# spin.net
KiCad netlist of a schematic drawn in EAGLE
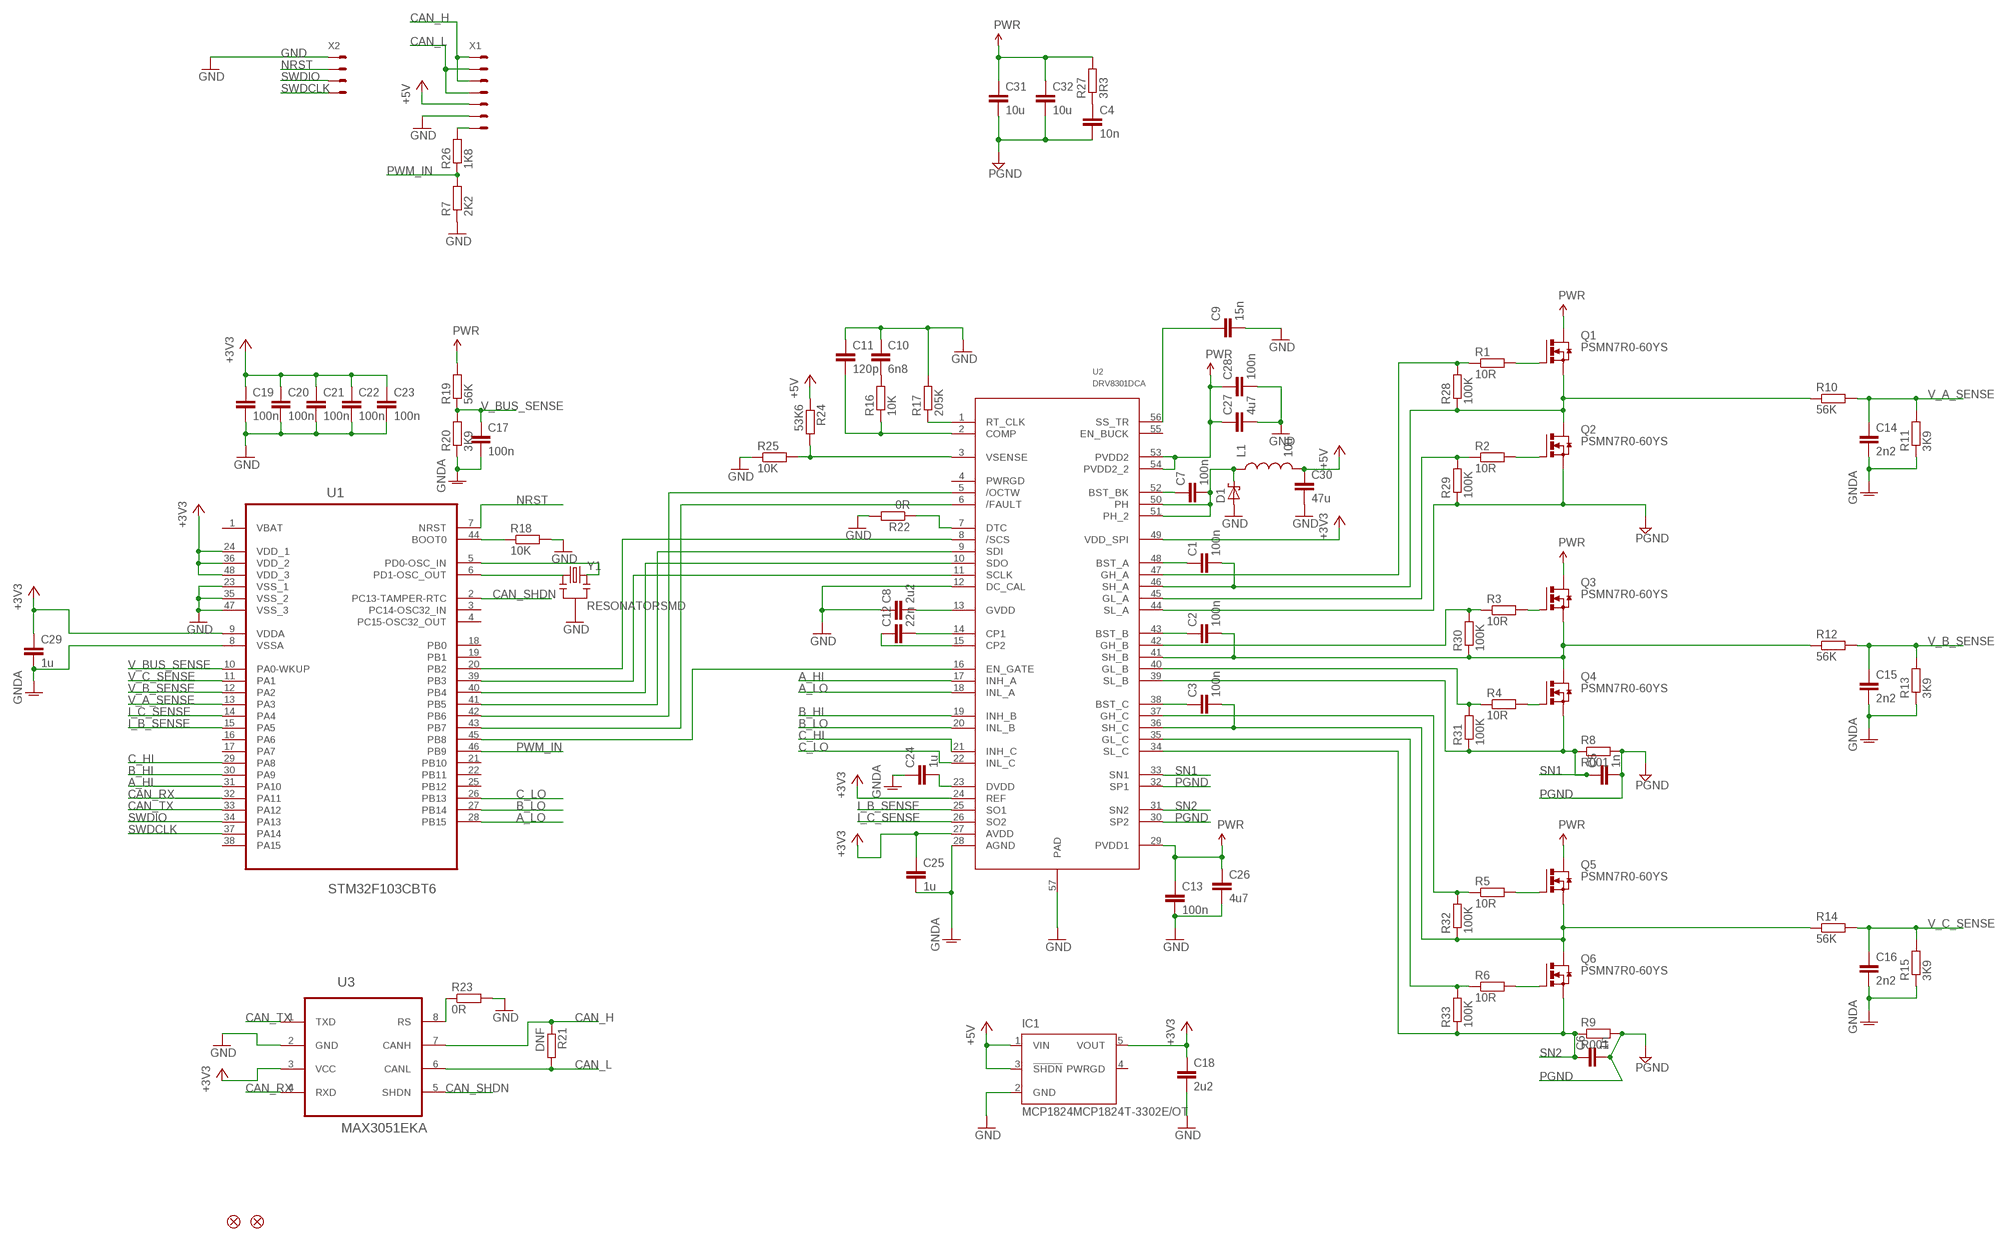
[diagram p0: schematic, sheet 1]

(export (version "E")
  (design (tool "Eeschema 10.0.6"))
  (components
    (comp (ref "C1")
      (value "100n")
      (footprint "eagle-import:C0603")
      (libsource (lib "eagle-import") (part "C-EUC0603"))
    )
    (comp (ref "C2")
      (value "100n")
      (footprint "eagle-import:C0603")
      (libsource (lib "eagle-import") (part "C-EUC0603"))
    )
    (comp (ref "C3")
      (value "100n")
      (footprint "eagle-import:C0603")
      (libsource (lib "eagle-import") (part "C-EUC0603"))
    )
    (comp (ref "C4")
      (value "10n")
      (footprint "eagle-import:C0603")
      (libsource (lib "eagle-import") (part "C-EUC0603"))
    )
    (comp (ref "C5")
      (value "1n")
      (footprint "eagle-import:C0603")
      (libsource (lib "eagle-import") (part "C-EUC0603"))
    )
    (comp (ref "C6")
      (value "1n")
      (footprint "eagle-import:C0603")
      (libsource (lib "eagle-import") (part "C-EUC0603"))
    )
    (comp (ref "C7")
      (value "100n")
      (footprint "eagle-import:C0603")
      (libsource (lib "eagle-import") (part "C-EUC0603"))
    )
    (comp (ref "C8")
      (value "2u2")
      (footprint "eagle-import:C0603")
      (libsource (lib "eagle-import") (part "C-EUC0603"))
    )
    (comp (ref "C9")
      (value "15n")
      (footprint "eagle-import:C0603")
      (libsource (lib "eagle-import") (part "C-EUC0603"))
    )
    (comp (ref "C10")
      (value "6n8")
      (footprint "eagle-import:C0603")
      (libsource (lib "eagle-import") (part "C-EUC0603"))
    )
    (comp (ref "C11")
      (value "120p")
      (footprint "eagle-import:C0603")
      (libsource (lib "eagle-import") (part "C-EUC0603"))
    )
    (comp (ref "C12")
      (value "22n")
      (footprint "eagle-import:C0603")
      (libsource (lib "eagle-import") (part "C-EUC0603"))
    )
    (comp (ref "C13")
      (value "100n")
      (footprint "eagle-import:C0603")
      (libsource (lib "eagle-import") (part "C-EUC0603"))
    )
    (comp (ref "C14")
      (value "2n2")
      (footprint "eagle-import:C0603")
      (libsource (lib "eagle-import") (part "C-EUC0603"))
    )
    (comp (ref "C15")
      (value "2n2")
      (footprint "eagle-import:C0603")
      (libsource (lib "eagle-import") (part "C-EUC0603"))
    )
    (comp (ref "C16")
      (value "2n2")
      (footprint "eagle-import:C0603")
      (libsource (lib "eagle-import") (part "C-EUC0603"))
    )
    (comp (ref "C17")
      (value "100n")
      (footprint "eagle-import:C0603")
      (libsource (lib "eagle-import") (part "C-EUC0603"))
    )
    (comp (ref "C18")
      (value "2u2")
      (footprint "eagle-import:C0603")
      (libsource (lib "eagle-import") (part "C-EUC0603"))
    )
    (comp (ref "C19")
      (value "100n")
      (footprint "eagle-import:C0603")
      (libsource (lib "eagle-import") (part "C-EUC0603"))
    )
    (comp (ref "C20")
      (value "100n")
      (footprint "eagle-import:C0603")
      (libsource (lib "eagle-import") (part "C-EUC0603"))
    )
    (comp (ref "C21")
      (value "100n")
      (footprint "eagle-import:C0603")
      (libsource (lib "eagle-import") (part "C-EUC0603"))
    )
    (comp (ref "C22")
      (value "100n")
      (footprint "eagle-import:C0603")
      (libsource (lib "eagle-import") (part "C-EUC0603"))
    )
    (comp (ref "C23")
      (value "100n")
      (footprint "eagle-import:C0603")
      (libsource (lib "eagle-import") (part "C-EUC0603"))
    )
    (comp (ref "C24")
      (value "1u")
      (footprint "eagle-import:C0603")
      (libsource (lib "eagle-import") (part "C-EUC0603"))
    )
    (comp (ref "C25")
      (value "1u")
      (footprint "eagle-import:C0603")
      (libsource (lib "eagle-import") (part "C-EUC0603"))
    )
    (comp (ref "C26")
      (value "4u7")
      (footprint "eagle-import:C0805")
      (libsource (lib "eagle-import") (part "C-EUC0805"))
    )
    (comp (ref "C27")
      (value "4u7")
      (footprint "eagle-import:C0805")
      (libsource (lib "eagle-import") (part "C-EUC0805"))
    )
    (comp (ref "C28")
      (value "100n")
      (footprint "eagle-import:C0603")
      (libsource (lib "eagle-import") (part "C-EUC0603"))
    )
    (comp (ref "C29")
      (value "1u")
      (footprint "eagle-import:C0603")
      (libsource (lib "eagle-import") (part "C-EUC0603"))
    )
    (comp (ref "C30")
      (value "47u")
      (footprint "eagle-import:1210")
      (libsource (lib "eagle-import") (part "CAP1210"))
    )
    (comp (ref "C31")
      (value "10u")
      (footprint "eagle-import:1210")
      (libsource (lib "eagle-import") (part "CAP1210"))
    )
    (comp (ref "C32")
      (value "10u")
      (footprint "eagle-import:1210")
      (libsource (lib "eagle-import") (part "CAP1210"))
    )
    (comp (ref "D1")
      (value "STPS1H100AF")
      (footprint "eagle-import:SMA")
      (libsource (lib "eagle-import") (part "STPS1H100AF"))
    )
    (comp (ref "IC1")
      (value "MCP1824MCP1824T-3302E/OT")
      (footprint "eagle-import:SOT23-5L")
      (libsource (lib "eagle-import") (part "MCP1824MCP1824T-3302E/OT"))
    )
    (comp (ref "JP1")
      (value "FIDUCIALUFIDUCIAL")
      (footprint "eagle-import:MICRO-FIDUCIAL")
      (libsource (lib "eagle-import") (part "FIDUCIALUFIDUCIAL"))
    )
    (comp (ref "JP2")
      (value "FIDUCIALUFIDUCIAL")
      (footprint "eagle-import:MICRO-FIDUCIAL")
      (libsource (lib "eagle-import") (part "FIDUCIALUFIDUCIAL"))
    )
    (comp (ref "L1")
      (value "10u")
      (footprint "eagle-import:NR6028")
      (libsource (lib "eagle-import") (part "INDUCTORNR6028"))
    )
    (comp (ref "Q1")
      (value "PSMN7R0-60YS")
      (footprint "eagle-import:POWER-SO8-UNIVERSAL")
      (libsource (lib "eagle-import") (part "PSMN7R0-60YS"))
    )
    (comp (ref "Q2")
      (value "PSMN7R0-60YS")
      (footprint "eagle-import:POWER-SO8-UNIVERSAL")
      (libsource (lib "eagle-import") (part "PSMN7R0-60YS"))
    )
    (comp (ref "Q3")
      (value "PSMN7R0-60YS")
      (footprint "eagle-import:POWER-SO8-UNIVERSAL")
      (libsource (lib "eagle-import") (part "PSMN7R0-60YS"))
    )
    (comp (ref "Q4")
      (value "PSMN7R0-60YS")
      (footprint "eagle-import:POWER-SO8-UNIVERSAL")
      (libsource (lib "eagle-import") (part "PSMN7R0-60YS"))
    )
    (comp (ref "Q5")
      (value "PSMN7R0-60YS")
      (footprint "eagle-import:POWER-SO8-UNIVERSAL")
      (libsource (lib "eagle-import") (part "PSMN7R0-60YS"))
    )
    (comp (ref "Q6")
      (value "PSMN7R0-60YS")
      (footprint "eagle-import:POWER-SO8-UNIVERSAL")
      (libsource (lib "eagle-import") (part "PSMN7R0-60YS"))
    )
    (comp (ref "R1")
      (value "10R")
      (footprint "eagle-import:R0603")
      (libsource (lib "eagle-import") (part "R-EU_R0603"))
    )
    (comp (ref "R2")
      (value "10R")
      (footprint "eagle-import:R0603")
      (libsource (lib "eagle-import") (part "R-EU_R0603"))
    )
    (comp (ref "R3")
      (value "10R")
      (footprint "eagle-import:R0603")
      (libsource (lib "eagle-import") (part "R-EU_R0603"))
    )
    (comp (ref "R4")
      (value "10R")
      (footprint "eagle-import:R0603")
      (libsource (lib "eagle-import") (part "R-EU_R0603"))
    )
    (comp (ref "R5")
      (value "10R")
      (footprint "eagle-import:R0603")
      (libsource (lib "eagle-import") (part "R-EU_R0603"))
    )
    (comp (ref "R6")
      (value "10R")
      (footprint "eagle-import:R0603")
      (libsource (lib "eagle-import") (part "R-EU_R0603"))
    )
    (comp (ref "R7")
      (value "2K2")
      (footprint "eagle-import:R0603")
      (libsource (lib "eagle-import") (part "R-EU_R0603"))
    )
    (comp (ref "R8")
      (value "R001")
      (footprint "eagle-import:R1210")
      (libsource (lib "eagle-import") (part "R-EU_R1210"))
    )
    (comp (ref "R9")
      (value "R001")
      (footprint "eagle-import:R1210")
      (libsource (lib "eagle-import") (part "R-EU_R1210"))
    )
    (comp (ref "R10")
      (value "56K")
      (footprint "eagle-import:R0603")
      (libsource (lib "eagle-import") (part "R-EU_R0603"))
    )
    (comp (ref "R11")
      (value "3K9")
      (footprint "eagle-import:R0603")
      (libsource (lib "eagle-import") (part "R-EU_R0603"))
    )
    (comp (ref "R12")
      (value "56K")
      (footprint "eagle-import:R0603")
      (libsource (lib "eagle-import") (part "R-EU_R0603"))
    )
    (comp (ref "R13")
      (value "3K9")
      (footprint "eagle-import:R0603")
      (libsource (lib "eagle-import") (part "R-EU_R0603"))
    )
    (comp (ref "R14")
      (value "56K")
      (footprint "eagle-import:R0603")
      (libsource (lib "eagle-import") (part "R-EU_R0603"))
    )
    (comp (ref "R15")
      (value "3K9")
      (footprint "eagle-import:R0603")
      (libsource (lib "eagle-import") (part "R-EU_R0603"))
    )
    (comp (ref "R16")
      (value "10K")
      (footprint "eagle-import:R0603")
      (libsource (lib "eagle-import") (part "R-EU_R0603"))
    )
    (comp (ref "R17")
      (value "205K")
      (footprint "eagle-import:R0603")
      (libsource (lib "eagle-import") (part "R-EU_R0603"))
    )
    (comp (ref "R18")
      (value "10K")
      (footprint "eagle-import:R0603")
      (libsource (lib "eagle-import") (part "R-EU_R0603"))
    )
    (comp (ref "R19")
      (value "56K")
      (footprint "eagle-import:R0603")
      (libsource (lib "eagle-import") (part "R-EU_R0603"))
    )
    (comp (ref "R20")
      (value "3K9")
      (footprint "eagle-import:R0603")
      (libsource (lib "eagle-import") (part "R-EU_R0603"))
    )
    (comp (ref "R21")
      (value "DNF")
      (footprint "eagle-import:R0603")
      (libsource (lib "eagle-import") (part "R-EU_R0603"))
    )
    (comp (ref "R22")
      (value "0R")
      (footprint "eagle-import:R0603")
      (libsource (lib "eagle-import") (part "R-EU_R0603"))
    )
    (comp (ref "R23")
      (value "0R")
      (footprint "eagle-import:R0603")
      (libsource (lib "eagle-import") (part "R-EU_R0603"))
    )
    (comp (ref "R24")
      (value "53K6")
      (footprint "eagle-import:R0603")
      (libsource (lib "eagle-import") (part "R-EU_R0603"))
    )
    (comp (ref "R25")
      (value "10K")
      (footprint "eagle-import:R0603")
      (libsource (lib "eagle-import") (part "R-EU_R0603"))
    )
    (comp (ref "R26")
      (value "1K8")
      (footprint "eagle-import:R0603")
      (libsource (lib "eagle-import") (part "R-EU_R0603"))
    )
    (comp (ref "R27")
      (value "3R3")
      (footprint "eagle-import:R0805")
      (libsource (lib "eagle-import") (part "R-EU_R0805"))
    )
    (comp (ref "R28")
      (value "100K")
      (footprint "eagle-import:R0603")
      (libsource (lib "eagle-import") (part "R-EU_R0603"))
    )
    (comp (ref "R29")
      (value "100K")
      (footprint "eagle-import:R0603")
      (libsource (lib "eagle-import") (part "R-EU_R0603"))
    )
    (comp (ref "R30")
      (value "100K")
      (footprint "eagle-import:R0603")
      (libsource (lib "eagle-import") (part "R-EU_R0603"))
    )
    (comp (ref "R31")
      (value "100K")
      (footprint "eagle-import:R0603")
      (libsource (lib "eagle-import") (part "R-EU_R0603"))
    )
    (comp (ref "R32")
      (value "100K")
      (footprint "eagle-import:R0603")
      (libsource (lib "eagle-import") (part "R-EU_R0603"))
    )
    (comp (ref "R33")
      (value "100K")
      (footprint "eagle-import:R0603")
      (libsource (lib "eagle-import") (part "R-EU_R0603"))
    )
    (comp (ref "U1")
      (value "STM32F103CBT6")
      (footprint "eagle-import:QFP50P900X900X160-48N")
      (libsource (lib "eagle-import") (part "STM32F103CBT6"))
    )
    (comp (ref "U2")
      (value "DRV8301DCA")
      (footprint "eagle-import:TSSOP56P")
      (libsource (lib "eagle-import") (part "DRV8301DCA"))
    )
    (comp (ref "U3")
      (value "MAX3051EKA")
      (footprint "eagle-import:SOT65P280X145-8N")
      (libsource (lib "eagle-import") (part "MAX3051EKA"))
    )
    (comp (ref "X1")
      (value "SM07B-SRSS-TB")
      (footprint "eagle-import:SM07B-SRSS-TB")
      (libsource (lib "eagle-import") (part "?M07B-SRSS-TBS"))
    )
    (comp (ref "X2")
      (value "SM04B-SRSS-TB")
      (footprint "eagle-import:SM04B-SRSS-TB")
      (libsource (lib "eagle-import") (part "?M04B-SRSS-TBS"))
    )
    (comp (ref "Y1")
      (value "RESONATORSMD")
      (footprint "eagle-import:RESONATOR-SMD")
      (libsource (lib "eagle-import") (part "RESONATORSMD"))
    )
  )
  (nets
    (net (code "1") (name "+3V3") (class "Default")
      (node (ref "C18") (pin "1") (pinfunction "1_1") (pintype "passive"))
      (node (ref "C19") (pin "1") (pinfunction "1_1") (pintype "passive"))
      (node (ref "C20") (pin "1") (pinfunction "1_1") (pintype "passive"))
      (node (ref "C21") (pin "1") (pinfunction "1_1") (pintype "passive"))
      (node (ref "C22") (pin "1") (pinfunction "1_1") (pintype "passive"))
      (node (ref "C23") (pin "1") (pinfunction "1_1") (pintype "passive"))
      (node (ref "C25") (pin "1") (pinfunction "1_1") (pintype "passive"))
      (node (ref "C29") (pin "1") (pinfunction "1_1") (pintype "passive"))
      (node (ref "IC1") (pin "5") (pinfunction "VOUT_5") (pintype "power_in"))
      (node (ref "U1") (pin "24") (pinfunction "VDD_1_24") (pintype "bidirectional"))
      (node (ref "U1") (pin "36") (pinfunction "VDD_2_36") (pintype "power_in"))
      (node (ref "U1") (pin "48") (pinfunction "VDD_3_48") (pintype "power_in"))
      (node (ref "U1") (pin "9") (pinfunction "VDDA_9") (pintype "power_in"))
      (node (ref "U2") (pin "24") (pinfunction "REF_24") (pintype "bidirectional"))
      (node (ref "U2") (pin "27") (pinfunction "AVDD_27") (pintype "bidirectional"))
      (node (ref "U2") (pin "49") (pinfunction "VDD_SPI_49") (pintype "bidirectional"))
      (node (ref "U3") (pin "3") (pinfunction "VCC_3") (pintype "power_in"))
    )
    (net (code "2") (name "+5V") (class "Default")
      (node (ref "C30") (pin "1") (pinfunction "1_1") (pintype "passive"))
      (node (ref "IC1") (pin "1") (pinfunction "VIN_1") (pintype "power_in"))
      (node (ref "IC1") (pin "3") (pinfunction "~{SHDN}_3") (pintype "input"))
      (node (ref "L1") (pin "2") (pinfunction "2_2") (pintype "passive"))
      (node (ref "R24") (pin "1") (pinfunction "1_1") (pintype "passive"))
      (node (ref "X1") (pin "5") (pinfunction "5_5") (pintype "passive"))
    )
    (net (code "3") (name "/A_HI") (class "Default")
      (node (ref "U1") (pin "31") (pinfunction "PA10_31") (pintype "bidirectional"))
      (node (ref "U2") (pin "17") (pinfunction "INH_A_17") (pintype "bidirectional"))
    )
    (net (code "4") (name "/A_LO") (class "Default")
      (node (ref "U1") (pin "28") (pinfunction "PB15_28") (pintype "bidirectional"))
      (node (ref "U2") (pin "18") (pinfunction "INL_A_18") (pintype "bidirectional"))
    )
    (net (code "5") (name "/B_HI") (class "Default")
      (node (ref "U1") (pin "30") (pinfunction "PA9_30") (pintype "bidirectional"))
      (node (ref "U2") (pin "19") (pinfunction "INH_B_19") (pintype "bidirectional"))
    )
    (net (code "6") (name "/B_LO") (class "Default")
      (node (ref "U1") (pin "27") (pinfunction "PB14_27") (pintype "bidirectional"))
      (node (ref "U2") (pin "20") (pinfunction "INL_B_20") (pintype "bidirectional"))
    )
    (net (code "7") (name "/CAN_H") (class "Default")
      (node (ref "R21") (pin "1") (pinfunction "1_1") (pintype "passive"))
      (node (ref "U3") (pin "7") (pinfunction "CANH_7") (pintype "input"))
      (node (ref "X1") (pin "1") (pinfunction "1_1") (pintype "passive"))
      (node (ref "X1") (pin "3") (pinfunction "3_3") (pintype "passive"))
    )
    (net (code "8") (name "/CAN_L") (class "Default")
      (node (ref "R21") (pin "2") (pinfunction "2_2") (pintype "passive"))
      (node (ref "U3") (pin "6") (pinfunction "CANL_6") (pintype "input"))
      (node (ref "X1") (pin "2") (pinfunction "2_2") (pintype "passive"))
      (node (ref "X1") (pin "4") (pinfunction "4_4") (pintype "passive"))
    )
    (net (code "9") (name "/CAN_RX") (class "Default")
      (node (ref "U1") (pin "32") (pinfunction "PA11_32") (pintype "power_in"))
      (node (ref "U3") (pin "4") (pinfunction "RXD_4") (pintype "output"))
    )
    (net (code "10") (name "/CAN_SHDN") (class "Default")
      (node (ref "U1") (pin "2") (pinfunction "PC13-TAMPER-RTC_2") (pintype "bidirectional"))
      (node (ref "U3") (pin "5") (pinfunction "SHDN_5") (pintype "input"))
    )
    (net (code "11") (name "/CAN_TX") (class "Default")
      (node (ref "U1") (pin "33") (pinfunction "PA12_33") (pintype "bidirectional"))
      (node (ref "U3") (pin "1") (pinfunction "TXD_1") (pintype "input"))
    )
    (net (code "12") (name "/C_HI") (class "Default")
      (node (ref "U1") (pin "29") (pinfunction "PA8_29") (pintype "bidirectional"))
      (node (ref "U2") (pin "21") (pinfunction "INH_C_21") (pintype "bidirectional"))
    )
    (net (code "13") (name "/C_LO") (class "Default")
      (node (ref "U1") (pin "26") (pinfunction "PB13_26") (pintype "bidirectional"))
      (node (ref "U2") (pin "22") (pinfunction "INL_C_22") (pintype "bidirectional"))
    )
    (net (code "14") (name "/I_B_SENSE") (class "Default")
      (node (ref "U1") (pin "15") (pinfunction "PA5_15") (pintype "bidirectional"))
      (node (ref "U2") (pin "25") (pinfunction "SO1_25") (pintype "bidirectional"))
    )
    (net (code "15") (name "/I_C_SENSE") (class "Default")
      (node (ref "U1") (pin "14") (pinfunction "PA4_14") (pintype "bidirectional"))
      (node (ref "U2") (pin "26") (pinfunction "SO2_26") (pintype "bidirectional"))
    )
    (net (code "16") (name "/NRST") (class "Default")
      (node (ref "U1") (pin "7") (pinfunction "NRST_7") (pintype "bidirectional"))
      (node (ref "X2") (pin "2") (pinfunction "2_2") (pintype "passive"))
    )
    (net (code "17") (name "/PWM_IN") (class "Default")
      (node (ref "R26") (pin "1") (pinfunction "1_1") (pintype "passive"))
      (node (ref "R7") (pin "2") (pinfunction "2_2") (pintype "passive"))
      (node (ref "U1") (pin "46") (pinfunction "PB9_46") (pintype "bidirectional"))
    )
    (net (code "18") (name "/SN1") (class "Default")
      (node (ref "C5") (pin "1") (pinfunction "1_1") (pintype "passive"))
      (node (ref "Q4") (pin "1") (pinfunction "S_1") (pintype "passive"))
      (node (ref "Q4") (pin "2") (pinfunction "S_2") (pintype "passive"))
      (node (ref "Q4") (pin "3") (pinfunction "S_3") (pintype "passive"))
      (node (ref "R31") (pin "1") (pinfunction "1_1") (pintype "passive"))
      (node (ref "R8") (pin "1") (pinfunction "1_1") (pintype "passive"))
      (node (ref "U2") (pin "33") (pinfunction "SN1_33") (pintype "bidirectional"))
      (node (ref "U2") (pin "39") (pinfunction "SL_B_39") (pintype "bidirectional"))
    )
    (net (code "19") (name "/SN2") (class "Default")
      (node (ref "C6") (pin "1") (pinfunction "1_1") (pintype "passive"))
      (node (ref "Q6") (pin "1") (pinfunction "S_1") (pintype "passive"))
      (node (ref "Q6") (pin "2") (pinfunction "S_2") (pintype "passive"))
      (node (ref "Q6") (pin "3") (pinfunction "S_3") (pintype "passive"))
      (node (ref "R33") (pin "1") (pinfunction "1_1") (pintype "passive"))
      (node (ref "R9") (pin "1") (pinfunction "1_1") (pintype "passive"))
      (node (ref "U2") (pin "31") (pinfunction "SN2_31") (pintype "bidirectional"))
      (node (ref "U2") (pin "34") (pinfunction "SL_C_34") (pintype "bidirectional"))
    )
    (net (code "20") (name "/SWDCLK") (class "Default")
      (node (ref "U1") (pin "37") (pinfunction "PA14_37") (pintype "bidirectional"))
      (node (ref "X2") (pin "4") (pinfunction "4_4") (pintype "passive"))
    )
    (net (code "21") (name "/SWDIO") (class "Default")
      (node (ref "U1") (pin "34") (pinfunction "PA13_34") (pintype "bidirectional"))
      (node (ref "X2") (pin "3") (pinfunction "3_3") (pintype "passive"))
    )
    (net (code "22") (name "/V_A_SENSE") (class "Default")
      (node (ref "C14") (pin "1") (pinfunction "1_1") (pintype "passive"))
      (node (ref "R10") (pin "2") (pinfunction "2_2") (pintype "passive"))
      (node (ref "R11") (pin "2") (pinfunction "2_2") (pintype "passive"))
      (node (ref "U1") (pin "13") (pinfunction "PA3_13") (pintype "bidirectional"))
    )
    (net (code "23") (name "/V_BUS_SENSE") (class "Default")
      (node (ref "C17") (pin "1") (pinfunction "1_1") (pintype "passive"))
      (node (ref "R19") (pin "1") (pinfunction "1_1") (pintype "passive"))
      (node (ref "R20") (pin "2") (pinfunction "2_2") (pintype "passive"))
      (node (ref "U1") (pin "10") (pinfunction "PA0-WKUP_10") (pintype "bidirectional"))
    )
    (net (code "24") (name "/V_B_SENSE") (class "Default")
      (node (ref "C15") (pin "1") (pinfunction "1_1") (pintype "passive"))
      (node (ref "R12") (pin "2") (pinfunction "2_2") (pintype "passive"))
      (node (ref "R13") (pin "2") (pinfunction "2_2") (pintype "passive"))
      (node (ref "U1") (pin "12") (pinfunction "PA2_12") (pintype "bidirectional"))
    )
    (net (code "25") (name "/V_C_SENSE") (class "Default")
      (node (ref "C16") (pin "1") (pinfunction "1_1") (pintype "passive"))
      (node (ref "R14") (pin "2") (pinfunction "2_2") (pintype "passive"))
      (node (ref "R15") (pin "2") (pinfunction "2_2") (pintype "passive"))
      (node (ref "U1") (pin "11") (pinfunction "PA1_11") (pintype "bidirectional"))
    )
    (net (code "26") (name "GND") (class "Default")
      (node (ref "C10") (pin "1") (pinfunction "1_1") (pintype "passive"))
      (node (ref "C11") (pin "1") (pinfunction "1_1") (pintype "passive"))
      (node (ref "C13") (pin "2") (pinfunction "2_2") (pintype "passive"))
      (node (ref "C18") (pin "2") (pinfunction "2_2") (pintype "passive"))
      (node (ref "C19") (pin "2") (pinfunction "2_2") (pintype "passive"))
      (node (ref "C20") (pin "2") (pinfunction "2_2") (pintype "passive"))
      (node (ref "C21") (pin "2") (pinfunction "2_2") (pintype "passive"))
      (node (ref "C22") (pin "2") (pinfunction "2_2") (pintype "passive"))
      (node (ref "C23") (pin "2") (pinfunction "2_2") (pintype "passive"))
      (node (ref "C26") (pin "2") (pinfunction "2_2") (pintype "passive"))
      (node (ref "C27") (pin "2") (pinfunction "2_2") (pintype "passive"))
      (node (ref "C28") (pin "2") (pinfunction "2_2") (pintype "passive"))
      (node (ref "C30") (pin "2") (pinfunction "2_2") (pintype "passive"))
      (node (ref "C8") (pin "1") (pinfunction "1_1") (pintype "passive"))
      (node (ref "C9") (pin "2") (pinfunction "2_2") (pintype "passive"))
      (node (ref "D1") (pin "A") (pinfunction "A_A") (pintype "passive"))
      (node (ref "IC1") (pin "2") (pinfunction "GND_2") (pintype "power_in"))
      (node (ref "R17") (pin "2") (pinfunction "2_2") (pintype "passive"))
      (node (ref "R18") (pin "2") (pinfunction "2_2") (pintype "passive"))
      (node (ref "R22") (pin "2") (pinfunction "2_2") (pintype "passive"))
      (node (ref "R23") (pin "2") (pinfunction "2_2") (pintype "passive"))
      (node (ref "R25") (pin "1") (pinfunction "1_1") (pintype "passive"))
      (node (ref "R7") (pin "1") (pinfunction "1_1") (pintype "passive"))
      (node (ref "U1") (pin "23") (pinfunction "VSS_1_23") (pintype "bidirectional"))
      (node (ref "U1") (pin "35") (pinfunction "VSS_2_35") (pintype "passive"))
      (node (ref "U1") (pin "47") (pinfunction "VSS_3_47") (pintype "passive"))
      (node (ref "U2") (pin "12") (pinfunction "DC_CAL_12") (pintype "bidirectional"))
      (node (ref "U2") (pin "57") (pinfunction "PAD_57") (pintype "bidirectional"))
      (node (ref "U3") (pin "2") (pinfunction "GND_2") (pintype "passive"))
      (node (ref "X1") (pin "6") (pinfunction "6_6") (pintype "passive"))
      (node (ref "X2") (pin "1") (pinfunction "1_1") (pintype "passive"))
      (node (ref "Y1") (pin "2") (pinfunction "2_2") (pintype "passive"))
    )
    (net (code "27") (name "GNDA") (class "Default")
      (node (ref "C14") (pin "2") (pinfunction "2_2") (pintype "passive"))
      (node (ref "C15") (pin "2") (pinfunction "2_2") (pintype "passive"))
      (node (ref "C16") (pin "2") (pinfunction "2_2") (pintype "passive"))
      (node (ref "C17") (pin "2") (pinfunction "2_2") (pintype "passive"))
      (node (ref "C24") (pin "1") (pinfunction "1_1") (pintype "passive"))
      (node (ref "C25") (pin "2") (pinfunction "2_2") (pintype "passive"))
      (node (ref "C29") (pin "2") (pinfunction "2_2") (pintype "passive"))
      (node (ref "R11") (pin "1") (pinfunction "1_1") (pintype "passive"))
      (node (ref "R13") (pin "1") (pinfunction "1_1") (pintype "passive"))
      (node (ref "R15") (pin "1") (pinfunction "1_1") (pintype "passive"))
      (node (ref "R20") (pin "1") (pinfunction "1_1") (pintype "passive"))
      (node (ref "U1") (pin "8") (pinfunction "VSSA_8") (pintype "passive"))
      (node (ref "U2") (pin "28") (pinfunction "AGND_28") (pintype "bidirectional"))
    )
    (net (code "28") (name "Net-(C4-Pad1)") (class "Default")
      (node (ref "C4") (pin "1") (pinfunction "1_1") (pintype "passive"))
      (node (ref "R27") (pin "1") (pinfunction "1_1") (pintype "passive"))
    )
    (net (code "29") (name "Net-(C10-Pad2)") (class "Default")
      (node (ref "C10") (pin "2") (pinfunction "2_2") (pintype "passive"))
      (node (ref "R16") (pin "2") (pinfunction "2_2") (pintype "passive"))
    )
    (net (code "30") (name "Net-(Q1-G)") (class "Default")
      (node (ref "Q1") (pin "4") (pinfunction "G_4") (pintype "passive"))
      (node (ref "R1") (pin "2") (pinfunction "2_2") (pintype "passive"))
    )
    (net (code "31") (name "Net-(Q2-G)") (class "Default")
      (node (ref "Q2") (pin "4") (pinfunction "G_4") (pintype "passive"))
      (node (ref "R2") (pin "2") (pinfunction "2_2") (pintype "passive"))
    )
    (net (code "32") (name "Net-(Q3-G)") (class "Default")
      (node (ref "Q3") (pin "4") (pinfunction "G_4") (pintype "passive"))
      (node (ref "R3") (pin "2") (pinfunction "2_2") (pintype "passive"))
    )
    (net (code "33") (name "Net-(Q4-G)") (class "Default")
      (node (ref "Q4") (pin "4") (pinfunction "G_4") (pintype "passive"))
      (node (ref "R4") (pin "2") (pinfunction "2_2") (pintype "passive"))
    )
    (net (code "34") (name "Net-(Q5-G)") (class "Default")
      (node (ref "Q5") (pin "4") (pinfunction "G_4") (pintype "passive"))
      (node (ref "R5") (pin "2") (pinfunction "2_2") (pintype "passive"))
    )
    (net (code "35") (name "Net-(Q6-G)") (class "Default")
      (node (ref "Q6") (pin "4") (pinfunction "G_4") (pintype "passive"))
      (node (ref "R6") (pin "2") (pinfunction "2_2") (pintype "passive"))
    )
    (net (code "36") (name "Net-(R26-Pad2)") (class "Default")
      (node (ref "R26") (pin "2") (pinfunction "2_2") (pintype "passive"))
      (node (ref "X1") (pin "7") (pinfunction "7_7") (pintype "passive"))
    )
    (net (code "37") (name "Net-(U1-BOOT0)") (class "Default")
      (node (ref "R18") (pin "1") (pinfunction "1_1") (pintype "passive"))
      (node (ref "U1") (pin "44") (pinfunction "BOOT0_44") (pintype "bidirectional"))
    )
    (net (code "38") (name "Net-(U1-PB2)") (class "Default")
      (node (ref "U1") (pin "20") (pinfunction "PB2_20") (pintype "bidirectional"))
      (node (ref "U2") (pin "8") (pinfunction "/SCS_8") (pintype "bidirectional"))
    )
    (net (code "39") (name "Net-(U1-PB3)") (class "Default")
      (node (ref "U1") (pin "39") (pinfunction "PB3_39") (pintype "bidirectional"))
      (node (ref "U2") (pin "11") (pinfunction "SCLK_11") (pintype "bidirectional"))
    )
    (net (code "40") (name "Net-(U1-PB4)") (class "Default")
      (node (ref "U1") (pin "40") (pinfunction "PB4_40") (pintype "bidirectional"))
      (node (ref "U2") (pin "10") (pinfunction "SDO_10") (pintype "bidirectional"))
    )
    (net (code "41") (name "Net-(U1-PB5)") (class "Default")
      (node (ref "U1") (pin "41") (pinfunction "PB5_41") (pintype "bidirectional"))
      (node (ref "U2") (pin "9") (pinfunction "SDI_9") (pintype "bidirectional"))
    )
    (net (code "42") (name "Net-(U1-PB6)") (class "Default")
      (node (ref "U1") (pin "42") (pinfunction "PB6_42") (pintype "bidirectional"))
      (node (ref "U2") (pin "5") (pinfunction "/OCTW_5") (pintype "bidirectional"))
    )
    (net (code "43") (name "Net-(U1-PB7)") (class "Default")
      (node (ref "U1") (pin "43") (pinfunction "PB7_43") (pintype "bidirectional"))
      (node (ref "U2") (pin "6") (pinfunction "/FAULT_6") (pintype "bidirectional"))
    )
    (net (code "44") (name "Net-(U1-PB8)") (class "Default")
      (node (ref "U1") (pin "45") (pinfunction "PB8_45") (pintype "bidirectional"))
      (node (ref "U2") (pin "16") (pinfunction "EN_GATE_16") (pintype "bidirectional"))
    )
    (net (code "45") (name "Net-(U1-PD0-OSC_IN)") (class "Default")
      (node (ref "U1") (pin "5") (pinfunction "PD0-OSC_IN_5") (pintype "bidirectional"))
      (node (ref "Y1") (pin "3") (pinfunction "3_3") (pintype "passive"))
    )
    (net (code "46") (name "Net-(U1-PD1-OSC_OUT)") (class "Default")
      (node (ref "U1") (pin "6") (pinfunction "PD1-OSC_OUT_6") (pintype "bidirectional"))
      (node (ref "Y1") (pin "1") (pinfunction "1_1") (pintype "passive"))
    )
    (net (code "47") (name "Net-(U2-BST_A)") (class "Default")
      (node (ref "C1") (pin "1") (pinfunction "1_1") (pintype "passive"))
      (node (ref "U2") (pin "48") (pinfunction "BST_A_48") (pintype "bidirectional"))
    )
    (net (code "48") (name "Net-(U2-BST_B)") (class "Default")
      (node (ref "C2") (pin "1") (pinfunction "1_1") (pintype "passive"))
      (node (ref "U2") (pin "43") (pinfunction "BST_B_43") (pintype "bidirectional"))
    )
    (net (code "49") (name "Net-(U2-BST_BK)") (class "Default")
      (node (ref "C7") (pin "1") (pinfunction "1_1") (pintype "passive"))
      (node (ref "U2") (pin "52") (pinfunction "BST_BK_52") (pintype "bidirectional"))
    )
    (net (code "50") (name "Net-(U2-BST_C)") (class "Default")
      (node (ref "C3") (pin "1") (pinfunction "1_1") (pintype "passive"))
      (node (ref "U2") (pin "38") (pinfunction "BST_C_38") (pintype "bidirectional"))
    )
    (net (code "51") (name "Net-(U2-COMP)") (class "Default")
      (node (ref "C11") (pin "2") (pinfunction "2_2") (pintype "passive"))
      (node (ref "R16") (pin "1") (pinfunction "1_1") (pintype "passive"))
      (node (ref "U2") (pin "2") (pinfunction "COMP_2") (pintype "bidirectional"))
    )
    (net (code "52") (name "Net-(U2-CP1)") (class "Default")
      (node (ref "C12") (pin "2") (pinfunction "2_2") (pintype "passive"))
      (node (ref "U2") (pin "14") (pinfunction "CP1_14") (pintype "bidirectional"))
    )
    (net (code "53") (name "Net-(U2-CP2)") (class "Default")
      (node (ref "C12") (pin "1") (pinfunction "1_1") (pintype "passive"))
      (node (ref "U2") (pin "15") (pinfunction "CP2_15") (pintype "bidirectional"))
    )
    (net (code "54") (name "Net-(U2-DTC)") (class "Default")
      (node (ref "R22") (pin "1") (pinfunction "1_1") (pintype "passive"))
      (node (ref "U2") (pin "7") (pinfunction "DTC_7") (pintype "bidirectional"))
    )
    (net (code "55") (name "Net-(U2-DVDD)") (class "Default")
      (node (ref "C24") (pin "2") (pinfunction "2_2") (pintype "passive"))
      (node (ref "U2") (pin "23") (pinfunction "DVDD_23") (pintype "bidirectional"))
    )
    (net (code "56") (name "Net-(U2-GH_A)") (class "Default")
      (node (ref "R1") (pin "1") (pinfunction "1_1") (pintype "passive"))
      (node (ref "R28") (pin "2") (pinfunction "2_2") (pintype "passive"))
      (node (ref "U2") (pin "47") (pinfunction "GH_A_47") (pintype "bidirectional"))
    )
    (net (code "57") (name "Net-(U2-GH_B)") (class "Default")
      (node (ref "R3") (pin "1") (pinfunction "1_1") (pintype "passive"))
      (node (ref "R30") (pin "2") (pinfunction "2_2") (pintype "passive"))
      (node (ref "U2") (pin "42") (pinfunction "GH_B_42") (pintype "bidirectional"))
    )
    (net (code "58") (name "Net-(U2-GH_C)") (class "Default")
      (node (ref "R32") (pin "2") (pinfunction "2_2") (pintype "passive"))
      (node (ref "R5") (pin "1") (pinfunction "1_1") (pintype "passive"))
      (node (ref "U2") (pin "37") (pinfunction "GH_C_37") (pintype "bidirectional"))
    )
    (net (code "59") (name "Net-(U2-GL_A)") (class "Default")
      (node (ref "R2") (pin "1") (pinfunction "1_1") (pintype "passive"))
      (node (ref "R29") (pin "2") (pinfunction "2_2") (pintype "passive"))
      (node (ref "U2") (pin "45") (pinfunction "GL_A_45") (pintype "bidirectional"))
    )
    (net (code "60") (name "Net-(U2-GL_B)") (class "Default")
      (node (ref "R31") (pin "2") (pinfunction "2_2") (pintype "passive"))
      (node (ref "R4") (pin "1") (pinfunction "1_1") (pintype "passive"))
      (node (ref "U2") (pin "40") (pinfunction "GL_B_40") (pintype "bidirectional"))
    )
    (net (code "61") (name "Net-(U2-GL_C)") (class "Default")
      (node (ref "R33") (pin "2") (pinfunction "2_2") (pintype "passive"))
      (node (ref "R6") (pin "1") (pinfunction "1_1") (pintype "passive"))
      (node (ref "U2") (pin "35") (pinfunction "GL_C_35") (pintype "bidirectional"))
    )
    (net (code "62") (name "Net-(U2-GVDD)") (class "Default")
      (node (ref "C8") (pin "2") (pinfunction "2_2") (pintype "passive"))
      (node (ref "U2") (pin "13") (pinfunction "GVDD_13") (pintype "bidirectional"))
    )
    (net (code "63") (name "Net-(U2-PH)") (class "Default")
      (node (ref "C7") (pin "2") (pinfunction "2_2") (pintype "passive"))
      (node (ref "D1") (pin "C") (pinfunction "C_C") (pintype "passive"))
      (node (ref "L1") (pin "1") (pinfunction "1_1") (pintype "passive"))
      (node (ref "U2") (pin "50") (pinfunction "PH_50") (pintype "bidirectional"))
      (node (ref "U2") (pin "51") (pinfunction "PH_2_51") (pintype "bidirectional"))
    )
    (net (code "64") (name "Net-(U2-RT_CLK)") (class "Default")
      (node (ref "R17") (pin "1") (pinfunction "1_1") (pintype "passive"))
      (node (ref "U2") (pin "1") (pinfunction "RT_CLK_1") (pintype "bidirectional"))
    )
    (net (code "65") (name "Net-(U2-SH_A)") (class "Default")
      (node (ref "C1") (pin "2") (pinfunction "2_2") (pintype "passive"))
      (node (ref "Q1") (pin "1") (pinfunction "S_1") (pintype "passive"))
      (node (ref "Q1") (pin "2") (pinfunction "S_2") (pintype "passive"))
      (node (ref "Q1") (pin "3") (pinfunction "S_3") (pintype "passive"))
      (node (ref "Q2") (pin "5") (pinfunction "D_5") (pintype "passive"))
      (node (ref "Q2") (pin "6") (pinfunction "D_6") (pintype "passive"))
      (node (ref "R10") (pin "1") (pinfunction "1_1") (pintype "passive"))
      (node (ref "R28") (pin "1") (pinfunction "1_1") (pintype "passive"))
      (node (ref "U2") (pin "46") (pinfunction "SH_A_46") (pintype "bidirectional"))
    )
    (net (code "66") (name "Net-(U2-SH_B)") (class "Default")
      (node (ref "C2") (pin "2") (pinfunction "2_2") (pintype "passive"))
      (node (ref "Q3") (pin "1") (pinfunction "S_1") (pintype "passive"))
      (node (ref "Q3") (pin "2") (pinfunction "S_2") (pintype "passive"))
      (node (ref "Q3") (pin "3") (pinfunction "S_3") (pintype "passive"))
      (node (ref "Q4") (pin "5") (pinfunction "D_5") (pintype "passive"))
      (node (ref "Q4") (pin "6") (pinfunction "D_6") (pintype "passive"))
      (node (ref "R12") (pin "1") (pinfunction "1_1") (pintype "passive"))
      (node (ref "R30") (pin "1") (pinfunction "1_1") (pintype "passive"))
      (node (ref "U2") (pin "41") (pinfunction "SH_B_41") (pintype "bidirectional"))
    )
    (net (code "67") (name "Net-(U2-SH_C)") (class "Default")
      (node (ref "C3") (pin "2") (pinfunction "2_2") (pintype "passive"))
      (node (ref "Q5") (pin "1") (pinfunction "S_1") (pintype "passive"))
      (node (ref "Q5") (pin "2") (pinfunction "S_2") (pintype "passive"))
      (node (ref "Q5") (pin "3") (pinfunction "S_3") (pintype "passive"))
      (node (ref "Q6") (pin "5") (pinfunction "D_5") (pintype "passive"))
      (node (ref "Q6") (pin "6") (pinfunction "D_6") (pintype "passive"))
      (node (ref "R14") (pin "1") (pinfunction "1_1") (pintype "passive"))
      (node (ref "R32") (pin "1") (pinfunction "1_1") (pintype "passive"))
      (node (ref "U2") (pin "36") (pinfunction "SH_C_36") (pintype "bidirectional"))
    )
    (net (code "68") (name "Net-(U2-SS_TR)") (class "Default")
      (node (ref "C9") (pin "1") (pinfunction "1_1") (pintype "passive"))
      (node (ref "U2") (pin "56") (pinfunction "SS_TR_56") (pintype "bidirectional"))
    )
    (net (code "69") (name "Net-(U2-VSENSE)") (class "Default")
      (node (ref "R24") (pin "2") (pinfunction "2_2") (pintype "passive"))
      (node (ref "R25") (pin "2") (pinfunction "2_2") (pintype "passive"))
      (node (ref "U2") (pin "3") (pinfunction "VSENSE_3") (pintype "bidirectional"))
    )
    (net (code "70") (name "Net-(U3-RS)") (class "Default")
      (node (ref "R23") (pin "1") (pinfunction "1_1") (pintype "passive"))
      (node (ref "U3") (pin "8") (pinfunction "RS_8") (pintype "input"))
    )
    (net (code "71") (name "PGND") (class "Default")
      (node (ref "C31") (pin "2") (pinfunction "2_2") (pintype "passive"))
      (node (ref "C32") (pin "2") (pinfunction "2_2") (pintype "passive"))
      (node (ref "C4") (pin "2") (pinfunction "2_2") (pintype "passive"))
      (node (ref "C5") (pin "2") (pinfunction "2_2") (pintype "passive"))
      (node (ref "C6") (pin "2") (pinfunction "2_2") (pintype "passive"))
      (node (ref "Q2") (pin "1") (pinfunction "S_1") (pintype "passive"))
      (node (ref "Q2") (pin "2") (pinfunction "S_2") (pintype "passive"))
      (node (ref "Q2") (pin "3") (pinfunction "S_3") (pintype "passive"))
      (node (ref "R29") (pin "1") (pinfunction "1_1") (pintype "passive"))
      (node (ref "R8") (pin "2") (pinfunction "2_2") (pintype "passive"))
      (node (ref "R9") (pin "2") (pinfunction "2_2") (pintype "passive"))
      (node (ref "U2") (pin "30") (pinfunction "SP2_30") (pintype "bidirectional"))
      (node (ref "U2") (pin "32") (pinfunction "SP1_32") (pintype "bidirectional"))
      (node (ref "U2") (pin "44") (pinfunction "SL_A_44") (pintype "bidirectional"))
    )
    (net (code "72") (name "PWR") (class "Default")
      (node (ref "C13") (pin "1") (pinfunction "1_1") (pintype "passive"))
      (node (ref "C26") (pin "1") (pinfunction "1_1") (pintype "passive"))
      (node (ref "C27") (pin "1") (pinfunction "1_1") (pintype "passive"))
      (node (ref "C28") (pin "1") (pinfunction "1_1") (pintype "passive"))
      (node (ref "C31") (pin "1") (pinfunction "1_1") (pintype "passive"))
      (node (ref "C32") (pin "1") (pinfunction "1_1") (pintype "passive"))
      (node (ref "Q1") (pin "5") (pinfunction "D_5") (pintype "passive"))
      (node (ref "Q1") (pin "6") (pinfunction "D_6") (pintype "passive"))
      (node (ref "Q3") (pin "5") (pinfunction "D_5") (pintype "passive"))
      (node (ref "Q3") (pin "6") (pinfunction "D_6") (pintype "passive"))
      (node (ref "Q5") (pin "5") (pinfunction "D_5") (pintype "passive"))
      (node (ref "Q5") (pin "6") (pinfunction "D_6") (pintype "passive"))
      (node (ref "R19") (pin "2") (pinfunction "2_2") (pintype "passive"))
      (node (ref "R27") (pin "2") (pinfunction "2_2") (pintype "passive"))
      (node (ref "U2") (pin "29") (pinfunction "PVDD1_29") (pintype "bidirectional"))
      (node (ref "U2") (pin "53") (pinfunction "PVDD2_53") (pintype "bidirectional"))
      (node (ref "U2") (pin "54") (pinfunction "PVDD2_2_54") (pintype "bidirectional"))
    )
    (net (code "73") (name "unconnected-(IC1-PWRGD-Pad4)") (class "Default")
      (node (ref "IC1") (pin "4") (pinfunction "PWRGD_4") (pintype "output"))
    )
    (net (code "74") (name "unconnected-(U1-PA6-Pad16)") (class "Default")
      (node (ref "U1") (pin "16") (pinfunction "PA6_16") (pintype "bidirectional"))
    )
    (net (code "75") (name "unconnected-(U1-PA7-Pad17)") (class "Default")
      (node (ref "U1") (pin "17") (pinfunction "PA7_17") (pintype "bidirectional"))
    )
    (net (code "76") (name "unconnected-(U1-PA15-Pad38)") (class "Default")
      (node (ref "U1") (pin "38") (pinfunction "PA15_38") (pintype "bidirectional"))
    )
    (net (code "77") (name "unconnected-(U1-PB0-Pad18)") (class "Default")
      (node (ref "U1") (pin "18") (pinfunction "PB0_18") (pintype "bidirectional"))
    )
    (net (code "78") (name "unconnected-(U1-PB1-Pad19)") (class "Default")
      (node (ref "U1") (pin "19") (pinfunction "PB1_19") (pintype "bidirectional"))
    )
    (net (code "79") (name "unconnected-(U1-PB10-Pad21)") (class "Default")
      (node (ref "U1") (pin "21") (pinfunction "PB10_21") (pintype "bidirectional"))
    )
    (net (code "80") (name "unconnected-(U1-PB11-Pad22)") (class "Default")
      (node (ref "U1") (pin "22") (pinfunction "PB11_22") (pintype "bidirectional"))
    )
    (net (code "81") (name "unconnected-(U1-PB12-Pad25)") (class "Default")
      (node (ref "U1") (pin "25") (pinfunction "PB12_25") (pintype "bidirectional"))
    )
    (net (code "82") (name "unconnected-(U1-PC14-OSC32_IN-Pad3)") (class "Default")
      (node (ref "U1") (pin "3") (pinfunction "PC14-OSC32_IN_3") (pintype "bidirectional"))
    )
    (net (code "83") (name "unconnected-(U1-PC15-OSC32_OUT-Pad4)") (class "Default")
      (node (ref "U1") (pin "4") (pinfunction "PC15-OSC32_OUT_4") (pintype "bidirectional"))
    )
    (net (code "84") (name "unconnected-(U1-VBAT-Pad1)") (class "Default")
      (node (ref "U1") (pin "1") (pinfunction "VBAT_1") (pintype "input"))
    )
    (net (code "85") (name "unconnected-(U2-EN_BUCK-Pad55)") (class "Default")
      (node (ref "U2") (pin "55") (pinfunction "EN_BUCK_55") (pintype "bidirectional"))
    )
    (net (code "86") (name "unconnected-(U2-PWRGD-Pad4)") (class "Default")
      (node (ref "U2") (pin "4") (pinfunction "PWRGD_4") (pintype "bidirectional"))
    )
  )
)
